# multiplex-logic-function.net
KiCad netlist of a schematic drawn in EAGLE
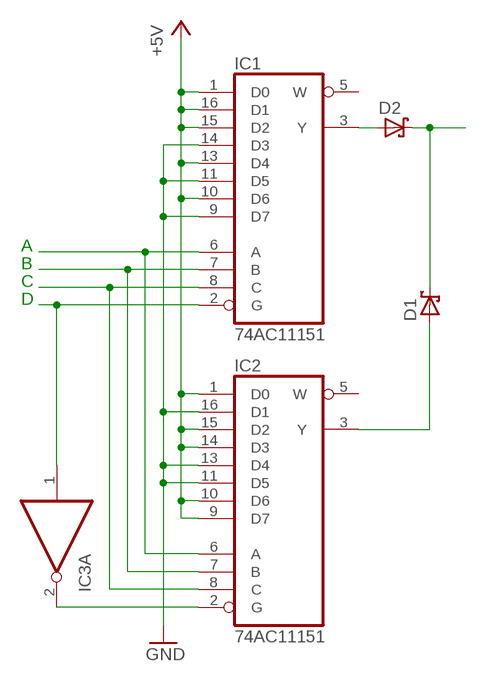
[diagram p0: schematic, sheet 1]

(export (version "E")
  (design (tool "Eeschema 10.0.6"))
  (components
    (comp (ref "D1")
      (value "BAS70")
      (footprint "eagle-import:SOT23")
      (libsource (lib "eagle-import") (part "BAS70"))
    )
    (comp (ref "D2")
      (value "BAS70")
      (footprint "eagle-import:SOT23")
      (libsource (lib "eagle-import") (part "BAS70"))
    )
    (comp (ref "IC1")
      (value "74AC11151")
      (footprint "eagle-import:DIL16")
      (libsource (lib "eagle-import") (part "74AC11151"))
    )
    (comp (ref "IC2")
      (value "74AC11151")
      (footprint "eagle-import:DIL16")
      (libsource (lib "eagle-import") (part "74AC11151"))
    )
    (comp (ref "IC3")
      (value "74AC06N")
      (footprint "eagle-import:DIL14")
      (libsource (lib "eagle-import") (part "7406NAC"))
    )
  )
  (nets
    (net (code "1") (name "+5V") (class "Default")
      (node (ref "IC1") (pin "1") (pinfunction "D0_1") (pintype "input"))
      (node (ref "IC1") (pin "10") (pinfunction "D6_10") (pintype "input"))
      (node (ref "IC1") (pin "13") (pinfunction "D4_13") (pintype "input"))
      (node (ref "IC1") (pin "15") (pinfunction "D2_15") (pintype "input"))
      (node (ref "IC1") (pin "16") (pinfunction "D1_16") (pintype "input"))
      (node (ref "IC2") (pin "1") (pinfunction "D0_1") (pintype "input"))
      (node (ref "IC2") (pin "10") (pinfunction "D6_10") (pintype "input"))
      (node (ref "IC2") (pin "14") (pinfunction "D3_14") (pintype "input"))
      (node (ref "IC2") (pin "15") (pinfunction "D2_15") (pintype "input"))
      (node (ref "IC2") (pin "9") (pinfunction "D7_9") (pintype "input"))
    )
    (net (code "2") (name "GND") (class "Default")
      (node (ref "IC1") (pin "11") (pinfunction "D5_11") (pintype "input"))
      (node (ref "IC1") (pin "14") (pinfunction "D3_14") (pintype "input"))
      (node (ref "IC1") (pin "9") (pinfunction "D7_9") (pintype "input"))
      (node (ref "IC2") (pin "11") (pinfunction "D5_11") (pintype "input"))
      (node (ref "IC2") (pin "13") (pinfunction "D4_13") (pintype "input"))
      (node (ref "IC2") (pin "16") (pinfunction "D1_16") (pintype "input"))
    )
    (net (code "3") (name "Net-(D1-A)") (class "Default")
      (node (ref "D1") (pin "1") (pinfunction "A_1") (pintype "passive"))
      (node (ref "IC2") (pin "3") (pinfunction "Y_3") (pintype "output"))
    )
    (net (code "4") (name "Net-(D1-C)") (class "Default")
      (node (ref "D1") (pin "3") (pinfunction "C_3") (pintype "passive"))
      (node (ref "D2") (pin "3") (pinfunction "C_3") (pintype "passive"))
    )
    (net (code "5") (name "Net-(D2-A)") (class "Default")
      (node (ref "D2") (pin "1") (pinfunction "A_1") (pintype "passive"))
      (node (ref "IC1") (pin "3") (pinfunction "Y_3") (pintype "output"))
    )
    (net (code "6") (name "Net-(IC1A-A)") (class "Default")
      (node (ref "IC1") (pin "6") (pinfunction "A_6") (pintype "input"))
      (node (ref "IC2") (pin "6") (pinfunction "A_6") (pintype "input"))
    )
    (net (code "7") (name "Net-(IC1A-B)") (class "Default")
      (node (ref "IC1") (pin "7") (pinfunction "B_7") (pintype "input"))
      (node (ref "IC2") (pin "7") (pinfunction "B_7") (pintype "input"))
    )
    (net (code "8") (name "Net-(IC1A-C)") (class "Default")
      (node (ref "IC1") (pin "8") (pinfunction "C_8") (pintype "input"))
      (node (ref "IC2") (pin "8") (pinfunction "C_8") (pintype "input"))
    )
    (net (code "9") (name "Net-(IC1A-G)") (class "Default")
      (node (ref "IC1") (pin "2") (pinfunction "G_2") (pintype "input"))
      (node (ref "IC3") (pin "1") (pinfunction "I_1") (pintype "input"))
    )
    (net (code "10") (name "Net-(IC2A-G)") (class "Default")
      (node (ref "IC2") (pin "2") (pinfunction "G_2") (pintype "input"))
      (node (ref "IC3") (pin "2") (pinfunction "O_2") (pintype "open_collector"))
    )
    (net (code "11") (name "unconnected-(IC1A-W-Pad5)") (class "Default")
      (node (ref "IC1") (pin "5") (pinfunction "W_5") (pintype "output"))
    )
    (net (code "12") (name "unconnected-(IC2A-W-Pad5)") (class "Default")
      (node (ref "IC2") (pin "5") (pinfunction "W_5") (pintype "output"))
    )
  )
)
